# OpenBook_v19.net
KiCad netlist of a schematic drawn in EAGLE
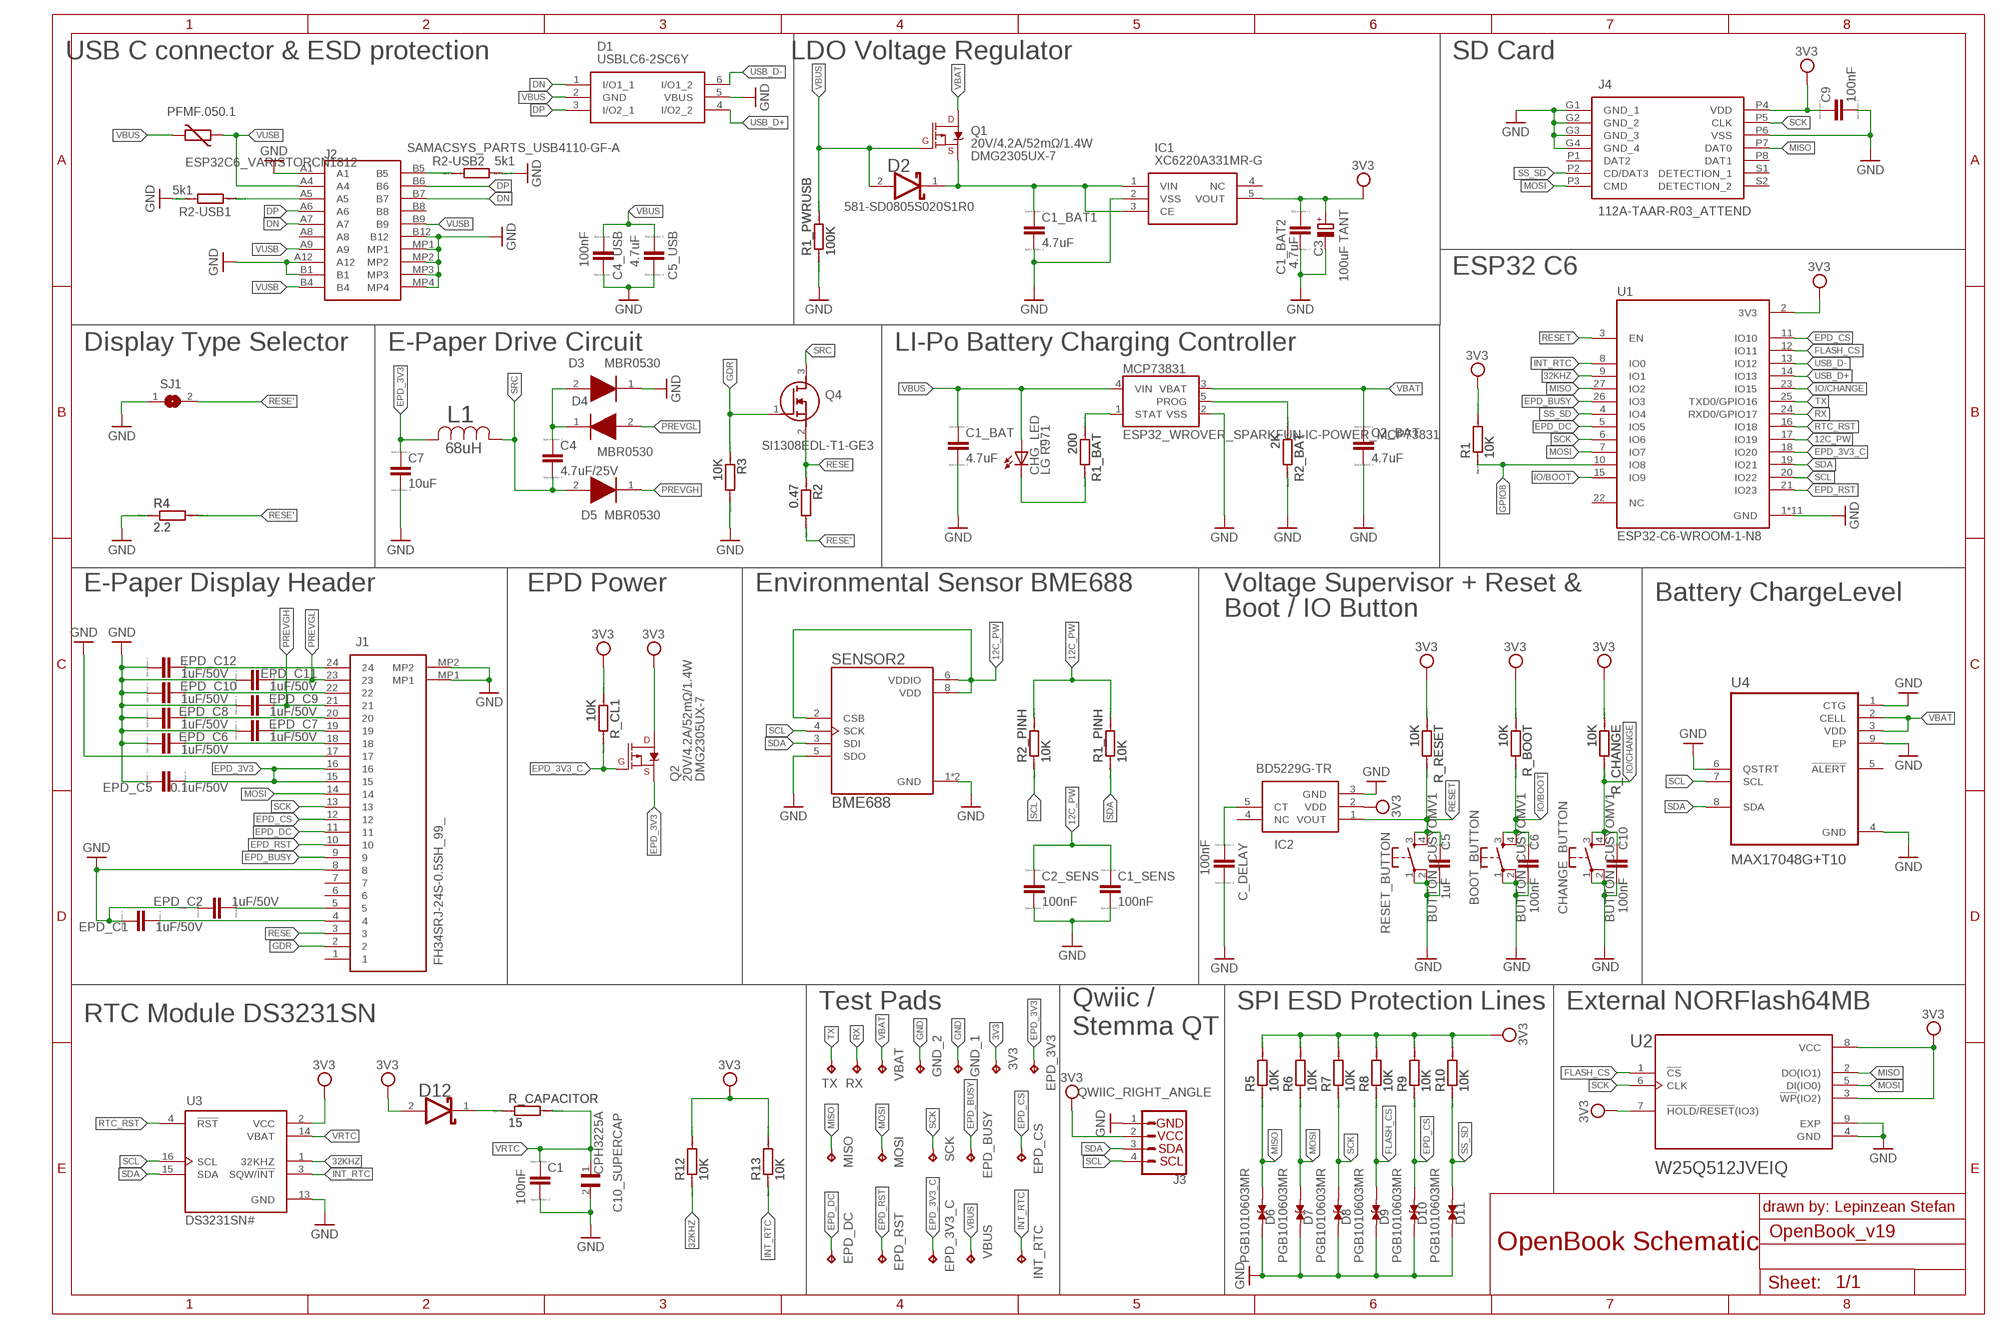
[diagram p0: schematic, sheet 1]

(export (version "E")
  (design (tool "Eeschema 10.0.6"))
  (components
    (comp (ref "3V3")
      (value "TPTP20R")
      (footprint "eagle-import:TP20R")
      (libsource (lib "eagle-import") (part "TPTP20R"))
    )
    (comp (ref "BOOT_BUTTON")
      (value "BUTTON_CUSYOMV1")
      (footprint "eagle-import:MYBUTTON")
      (libsource (lib "eagle-import") (part "BUTTON_CUSYOMV1"))
    )
    (comp (ref "C1")
      (value "100nF")
      (footprint "eagle-import:EAGLE-LTSPICE_C0402")
      (libsource (lib "eagle-import") (part "EAGLE-LTSPICE_CC0402"))
    )
    (comp (ref "C1_BAT")
      (value "4.7uF")
      (footprint "eagle-import:EAGLE-LTSPICE_C0402")
      (libsource (lib "eagle-import") (part "EAGLE-LTSPICE_CC0402"))
    )
    (comp (ref "C1_BAT1")
      (value "4.7uF")
      (footprint "eagle-import:EAGLE-LTSPICE_C0402")
      (libsource (lib "eagle-import") (part "EAGLE-LTSPICE_CC0402"))
    )
    (comp (ref "C1_BAT2")
      (value "4.7uF")
      (footprint "eagle-import:EAGLE-LTSPICE_C0402")
      (libsource (lib "eagle-import") (part "EAGLE-LTSPICE_CC0402"))
    )
    (comp (ref "C1_SENS")
      (value "100nF")
      (footprint "eagle-import:EAGLE-LTSPICE_C0402")
      (libsource (lib "eagle-import") (part "EAGLE-LTSPICE_CC0402"))
    )
    (comp (ref "C2_BAT")
      (value "4.7uF")
      (footprint "eagle-import:EAGLE-LTSPICE_C0402")
      (libsource (lib "eagle-import") (part "EAGLE-LTSPICE_CC0402"))
    )
    (comp (ref "C2_SENS")
      (value "100nF")
      (footprint "eagle-import:EAGLE-LTSPICE_C0402")
      (libsource (lib "eagle-import") (part "EAGLE-LTSPICE_CC0402"))
    )
    (comp (ref "C3")
      (value "100uF TANT")
      (footprint "eagle-import:RCL_CT3528")
      (libsource (lib "eagle-import") (part "RCL_CPOL-EUCT3528"))
    )
    (comp (ref "C4")
      (value "4.7uF/25V")
      (footprint "eagle-import:EAGLE-LTSPICE_C0402")
      (libsource (lib "eagle-import") (part "EAGLE-LTSPICE_CC0402"))
    )
    (comp (ref "C4_USB")
      (value "100nF")
      (footprint "eagle-import:EAGLE-LTSPICE_C0402")
      (libsource (lib "eagle-import") (part "EAGLE-LTSPICE_CC0402"))
    )
    (comp (ref "C5")
      (value "1uF")
      (footprint "eagle-import:EAGLE-LTSPICE_C0402")
      (libsource (lib "eagle-import") (part "EAGLE-LTSPICE_CC0402"))
    )
    (comp (ref "C5_USB")
      (value "4.7uF")
      (footprint "eagle-import:EAGLE-LTSPICE_C0402")
      (libsource (lib "eagle-import") (part "EAGLE-LTSPICE_CC0402"))
    )
    (comp (ref "C6")
      (value "100nF")
      (footprint "eagle-import:EAGLE-LTSPICE_C0402")
      (libsource (lib "eagle-import") (part "EAGLE-LTSPICE_CC0402"))
    )
    (comp (ref "C7")
      (value "10uF")
      (footprint "eagle-import:EAGLE-LTSPICE_C0402")
      (libsource (lib "eagle-import") (part "EAGLE-LTSPICE_CC0402"))
    )
    (comp (ref "C9")
      (value "100nF")
      (footprint "eagle-import:EAGLE-LTSPICE_C0402")
      (libsource (lib "eagle-import") (part "EAGLE-LTSPICE_CC0402"))
    )
    (comp (ref "C10")
      (value "100nF")
      (footprint "eagle-import:EAGLE-LTSPICE_C0402")
      (libsource (lib "eagle-import") (part "EAGLE-LTSPICE_CC0402"))
    )
    (comp (ref "C10_SUPERCAP")
      (value "CPH3225A")
      (footprint "eagle-import:CAPCP3225X100N")
      (fields (field (name "MF") "Seiko Instruments"))
      (libsource (lib "eagle-import") (part "CPH3225A"))
    )
    (comp (ref "CHANGE_BUTTON")
      (value "BUTTON_CUSYOMV1")
      (footprint "eagle-import:MYBUTTON")
      (libsource (lib "eagle-import") (part "BUTTON_CUSYOMV1"))
    )
    (comp (ref "CHG_LED")
      (value "LG R971")
      (footprint "eagle-import:ADAFRUIT_CHIP-LED0603")
      (libsource (lib "eagle-import") (part "ADAFRUIT_LEDCHIP-LED0603"))
    )
    (comp (ref "C_DELAY")
      (value "100nF")
      (footprint "eagle-import:EAGLE-LTSPICE_C0402")
      (libsource (lib "eagle-import") (part "EAGLE-LTSPICE_CC0402"))
    )
    (comp (ref "D1")
      (value "USBLC6-2SC6Y")
      (footprint "eagle-import:SOT95P280X145-6N")
      (fields (field (name "MF") "STMicroelectronics"))
      (libsource (lib "eagle-import") (part "USBLC6-2SC6Y"))
    )
    (comp (ref "D2")
      (value "ESP32_WROVER_AVX---SD0805S020S1R0_AVX_SD0805S020S1R0_0_0AVX_SD0805S020S1R0_0_0")
      (footprint "eagle-import:ESP32_WROVER_AVX---SD0805S020S1R0_AVX_SD0805S020S1R0_0")
      (fields
        (field (name "DIGIKEY_PART_NUMBER") "478-7800-1-ND")
        (field (name "MF") "AVX")
        (field (name "MOUSER_PART_NUMBER") "581-SD0805S020S1R0")
      )
      (libsource (lib "eagle-import") (part "ESP32_WROVER_AVX---SD0805S020S1R0_AVX_SD0805S020S1R0_0_0AVX_SD0805S020S1R0_0_0"))
    )
    (comp (ref "D3")
      (value "MBR0530")
      (footprint "eagle-import:SOD3716X135N")
      (fields (field (name "MF") "ON Semiconductor"))
      (libsource (lib "eagle-import") (part "MBR0530"))
    )
    (comp (ref "D4")
      (value "MBR0530")
      (footprint "eagle-import:SOD3716X135N")
      (fields (field (name "MF") "ON Semiconductor"))
      (libsource (lib "eagle-import") (part "MBR0530"))
    )
    (comp (ref "D5")
      (value "MBR0530")
      (footprint "eagle-import:SOD3716X135N")
      (fields (field (name "MF") "ON Semiconductor"))
      (libsource (lib "eagle-import") (part "MBR0530"))
    )
    (comp (ref "D6")
      (value "PGB1010603MR")
      (footprint "eagle-import:DIOC1608X36N")
      (fields (field (name "MF") "Littelfuse Inc."))
      (libsource (lib "eagle-import") (part "PGB1010603MR"))
    )
    (comp (ref "D7")
      (value "PGB1010603MR")
      (footprint "eagle-import:DIOC1608X36N")
      (fields (field (name "MF") "Littelfuse Inc."))
      (libsource (lib "eagle-import") (part "PGB1010603MR"))
    )
    (comp (ref "D8")
      (value "PGB1010603MR")
      (footprint "eagle-import:DIOC1608X36N")
      (fields (field (name "MF") "Littelfuse Inc."))
      (libsource (lib "eagle-import") (part "PGB1010603MR"))
    )
    (comp (ref "D9")
      (value "PGB1010603MR")
      (footprint "eagle-import:DIOC1608X36N")
      (fields (field (name "MF") "Littelfuse Inc."))
      (libsource (lib "eagle-import") (part "PGB1010603MR"))
    )
    (comp (ref "D10")
      (value "PGB1010603MR")
      (footprint "eagle-import:DIOC1608X36N")
      (fields (field (name "MF") "Littelfuse Inc."))
      (libsource (lib "eagle-import") (part "PGB1010603MR"))
    )
    (comp (ref "D11")
      (value "PGB1010603MR")
      (footprint "eagle-import:DIOC1608X36N")
      (fields (field (name "MF") "Littelfuse Inc."))
      (libsource (lib "eagle-import") (part "PGB1010603MR"))
    )
    (comp (ref "D12")
      (value "ESP32_WROVER_AVX---SD0805S020S1R0_AVX_SD0805S020S1R0_0_0AVX_SD0805S020S1R0_0_0")
      (footprint "eagle-import:ESP32_WROVER_AVX---SD0805S020S1R0_AVX_SD0805S020S1R0_0")
      (fields
        (field (name "DIGIKEY_PART_NUMBER") "478-7800-1-ND")
        (field (name "MF") "AVX")
        (field (name "MOUSER_PART_NUMBER") "581-SD0805S020S1R0")
      )
      (libsource (lib "eagle-import") (part "ESP32_WROVER_AVX---SD0805S020S1R0_AVX_SD0805S020S1R0_0_0AVX_SD0805S020S1R0_0_0"))
    )
    (comp (ref "EPD_3V3")
      (value "TPTP20R")
      (footprint "eagle-import:TP20R")
      (libsource (lib "eagle-import") (part "TPTP20R"))
    )
    (comp (ref "EPD_3V3_C")
      (value "TPTP20R")
      (footprint "eagle-import:TP20R")
      (libsource (lib "eagle-import") (part "TPTP20R"))
    )
    (comp (ref "EPD_BUSY")
      (value "TPTP20R")
      (footprint "eagle-import:TP20R")
      (libsource (lib "eagle-import") (part "TPTP20R"))
    )
    (comp (ref "EPD_C1")
      (value "1uF/50V")
      (footprint "eagle-import:EAGLE-LTSPICE_C0402")
      (libsource (lib "eagle-import") (part "EAGLE-LTSPICE_CC0402"))
    )
    (comp (ref "EPD_C2")
      (value "1uF/50V")
      (footprint "eagle-import:EAGLE-LTSPICE_C0402")
      (libsource (lib "eagle-import") (part "EAGLE-LTSPICE_CC0402"))
    )
    (comp (ref "EPD_C5")
      (value "0.1uF/50V")
      (footprint "eagle-import:EAGLE-LTSPICE_C0402")
      (libsource (lib "eagle-import") (part "EAGLE-LTSPICE_CC0402"))
    )
    (comp (ref "EPD_C6")
      (value "1uF/50V")
      (footprint "eagle-import:EAGLE-LTSPICE_C0402")
      (libsource (lib "eagle-import") (part "EAGLE-LTSPICE_CC0402"))
    )
    (comp (ref "EPD_C7")
      (value "1uF/50V")
      (footprint "eagle-import:EAGLE-LTSPICE_C0402")
      (libsource (lib "eagle-import") (part "EAGLE-LTSPICE_CC0402"))
    )
    (comp (ref "EPD_C8")
      (value "1uF/50V")
      (footprint "eagle-import:EAGLE-LTSPICE_C0402")
      (libsource (lib "eagle-import") (part "EAGLE-LTSPICE_CC0402"))
    )
    (comp (ref "EPD_C9")
      (value "1uF/50V")
      (footprint "eagle-import:EAGLE-LTSPICE_C0402")
      (libsource (lib "eagle-import") (part "EAGLE-LTSPICE_CC0402"))
    )
    (comp (ref "EPD_C10")
      (value "1uF/50V")
      (footprint "eagle-import:EAGLE-LTSPICE_C0402")
      (libsource (lib "eagle-import") (part "EAGLE-LTSPICE_CC0402"))
    )
    (comp (ref "EPD_C11")
      (value "1uF/50V")
      (footprint "eagle-import:EAGLE-LTSPICE_C0402")
      (libsource (lib "eagle-import") (part "EAGLE-LTSPICE_CC0402"))
    )
    (comp (ref "EPD_C12")
      (value "1uF/50V")
      (footprint "eagle-import:EAGLE-LTSPICE_C0402")
      (libsource (lib "eagle-import") (part "EAGLE-LTSPICE_CC0402"))
    )
    (comp (ref "EPD_CS")
      (value "TPTP20R")
      (footprint "eagle-import:TP20R")
      (libsource (lib "eagle-import") (part "TPTP20R"))
    )
    (comp (ref "EPD_DC")
      (value "TPTP20R")
      (footprint "eagle-import:TP20R")
      (libsource (lib "eagle-import") (part "TPTP20R"))
    )
    (comp (ref "EPD_RST")
      (value "TPTP20R")
      (footprint "eagle-import:TP20R")
      (libsource (lib "eagle-import") (part "TPTP20R"))
    )
    (comp (ref "GND_1")
      (value "TPTP20R")
      (footprint "eagle-import:TP20R")
      (libsource (lib "eagle-import") (part "TPTP20R"))
    )
    (comp (ref "GND_2")
      (value "TPTP20R")
      (footprint "eagle-import:TP20R")
      (libsource (lib "eagle-import") (part "TPTP20R"))
    )
    (comp (ref "IC1")
      (value "XC6220A331MR-G")
      (footprint "eagle-import:SOT95P280X125-5N")
      (fields (field (name "MOUSER_PART_NUMBER") "865-XC6220A331MR-G"))
      (libsource (lib "eagle-import") (part "XC6220A331MR-G"))
    )
    (comp (ref "IC2")
      (value "BD5229G-TR")
      (footprint "eagle-import:SOT95P280X120-5N")
      (fields (field (name "MOUSER_PART_NUMBER") "755-BD5229G-TR"))
      (libsource (lib "eagle-import") (part "BD5229G-TR"))
    )
    (comp (ref "INT_RTC")
      (value "TPTP20R")
      (footprint "eagle-import:TP20R")
      (libsource (lib "eagle-import") (part "TPTP20R"))
    )
    (comp (ref "J1")
      (value "FH34SRJ-24S-0.5SH_99_")
      (footprint "eagle-import:FH34SRJ24S05SH99")
      (fields
        (field (name "MANUFACTURER_PART_NUMBER") "FH34SRJ-24S-0.5SH(99)")
        (field (name "MOUSER_PART_NUMBER") "798-FH34SRJ24S05SH99")
      )
      (libsource (lib "eagle-import") (part "FH34SRJ-24S-0.5SH_99_"))
    )
    (comp (ref "J2")
      (value "SAMACSYS_PARTS_USB4110-GF-A")
      (footprint "eagle-import:SAMACSYS_PARTS_USB4110GFA")
      (fields
        (field (name "MANUFACTURER_PART_NUMBER") "USB4110-GF-A")
        (field (name "MOUSER_PART_NUMBER") "640-USB4110-GF-A")
      )
      (libsource (lib "eagle-import") (part "SAMACSYS_PARTS_USB4110-GF-A"))
    )
    (comp (ref "J3")
      (value "QWIIC_RIGHT_ANGLE")
      (footprint "eagle-import:JST04_1MM_RA")
      (libsource (lib "eagle-import") (part "QWIIC_CONNECTORJS-1MM"))
    )
    (comp (ref "J4")
      (value "112A-TAAR-R03_ATTEND")
      (footprint "eagle-import:112ATAARR03ATTEND")
      (fields (field (name "MANUFACTURER_PART_NUMBER") "112A-TAAR-R03 ATTEND"))
      (libsource (lib "eagle-import") (part "112A-TAAR-R03_ATTEND"))
    )
    (comp (ref "L1")
      (value "68uH")
      (footprint "eagle-import:IND_4828-WE-TPC_WRE")
      (fields
        (field (name "MANUFACTURER_PART_NUMBER") "744043680")
        (field (name "COPYRIGHT") "Copyright (C) 2024 Ultra Librarian. All rights reserved.")
      )
      (libsource (lib "eagle-import") (part "744043680IND_4828-WE-TPC_WRE"))
    )
    (comp (ref "MCP73831")
      (value "ESP32_WROVER_SPARKFUN-IC-POWER_MCP73831")
      (footprint "eagle-import:ESP32_WROVER_SPARKFUN-IC-POWER_SOT23-5")
      (libsource (lib "eagle-import") (part "ESP32_WROVER_SPARKFUN-IC-POWER_MCP73831"))
    )
    (comp (ref "MISO")
      (value "TPTP20R")
      (footprint "eagle-import:TP20R")
      (libsource (lib "eagle-import") (part "TPTP20R"))
    )
    (comp (ref "MOSI")
      (value "TPTP20R")
      (footprint "eagle-import:TP20R")
      (libsource (lib "eagle-import") (part "TPTP20R"))
    )
    (comp (ref "PFMF.050.1")
      (value "ESP32C6_VARISTORCN1812")
      (footprint "eagle-import:ESP32C6_VARISTOR_CT_CN1812")
      (libsource (lib "eagle-import") (part "ESP32C6_VARISTORCN1812"))
    )
    (comp (ref "Q1")
      (value "20V/4.2A/52mΩ/1.4W")
      (footprint "eagle-import:ESP32_WROVER_SPARKFUN-DISCRETESEMI_SOT23-3")
      (fields (field (name "PROD_ID") "DMG2305UX-7"))
      (libsource (lib "eagle-import") (part "ESP32_WROVER_SPARKFUN-DISCRETESEMI_MOSFET_PCH-DMG2305UX-7"))
    )
    (comp (ref "Q2")
      (value "20V/4.2A/52mΩ/1.4W")
      (footprint "eagle-import:ESP32_WROVER_SPARKFUN-DISCRETESEMI_SOT23-3")
      (fields (field (name "PROD_ID") "DMG2305UX-7"))
      (libsource (lib "eagle-import") (part "ESP32_WROVER_SPARKFUN-DISCRETESEMI_MOSFET_PCH-DMG2305UX-7"))
    )
    (comp (ref "Q4")
      (value "SI1308EDL-T1-GE3")
      (footprint "eagle-import:SOT65P210X110-3N")
      (fields (field (name "MF") "Vishay Siliconix"))
      (libsource (lib "eagle-import") (part "SI1308EDL-T1-GE3"))
    )
    (comp (ref "R1")
      (value "10K")
      (footprint "eagle-import:R0402")
      (libsource (lib "eagle-import") (part "ESP32_WROVER_EAGLE-LTSPICE_RR0402"))
    )
    (comp (ref "R1_BAT")
      (value "200")
      (footprint "eagle-import:R0402")
      (libsource (lib "eagle-import") (part "ESP32_WROVER_EAGLE-LTSPICE_RR0402"))
    )
    (comp (ref "R1_PINH")
      (value "10K")
      (footprint "eagle-import:R0402")
      (libsource (lib "eagle-import") (part "ESP32_WROVER_EAGLE-LTSPICE_RR0402"))
    )
    (comp (ref "R1_PWRUSB")
      (value "100K")
      (footprint "eagle-import:R0402")
      (libsource (lib "eagle-import") (part "ESP32_WROVER_EAGLE-LTSPICE_RR0402"))
    )
    (comp (ref "R2")
      (value "0.47")
      (footprint "eagle-import:R0402")
      (libsource (lib "eagle-import") (part "ESP32_WROVER_EAGLE-LTSPICE_RR0402"))
    )
    (comp (ref "R2-USB1")
      (value "5k1")
      (footprint "eagle-import:R0402")
      (libsource (lib "eagle-import") (part "ESP32_WROVER_EAGLE-LTSPICE_RR0402"))
    )
    (comp (ref "R2-USB2")
      (value "5k1")
      (footprint "eagle-import:R0402")
      (libsource (lib "eagle-import") (part "ESP32_WROVER_EAGLE-LTSPICE_RR0402"))
    )
    (comp (ref "R2_BAT")
      (value "2K")
      (footprint "eagle-import:R0402")
      (libsource (lib "eagle-import") (part "ESP32_WROVER_EAGLE-LTSPICE_RR0402"))
    )
    (comp (ref "R2_PINH")
      (value "10K")
      (footprint "eagle-import:R0402")
      (libsource (lib "eagle-import") (part "ESP32_WROVER_EAGLE-LTSPICE_RR0402"))
    )
    (comp (ref "R3")
      (value "10K")
      (footprint "eagle-import:R0402")
      (libsource (lib "eagle-import") (part "ESP32_WROVER_EAGLE-LTSPICE_RR0402"))
    )
    (comp (ref "R4")
      (value "2.2")
      (footprint "eagle-import:R0402")
      (libsource (lib "eagle-import") (part "ESP32_WROVER_EAGLE-LTSPICE_RR0402"))
    )
    (comp (ref "R5")
      (value "10K")
      (footprint "eagle-import:R0402")
      (libsource (lib "eagle-import") (part "ESP32_WROVER_EAGLE-LTSPICE_RR0402"))
    )
    (comp (ref "R6")
      (value "10K")
      (footprint "eagle-import:R0402")
      (libsource (lib "eagle-import") (part "ESP32_WROVER_EAGLE-LTSPICE_RR0402"))
    )
    (comp (ref "R7")
      (value "10K")
      (footprint "eagle-import:R0402")
      (libsource (lib "eagle-import") (part "ESP32_WROVER_EAGLE-LTSPICE_RR0402"))
    )
    (comp (ref "R8")
      (value "10K")
      (footprint "eagle-import:R0402")
      (libsource (lib "eagle-import") (part "ESP32_WROVER_EAGLE-LTSPICE_RR0402"))
    )
    (comp (ref "R9")
      (value "10K")
      (footprint "eagle-import:R0402")
      (libsource (lib "eagle-import") (part "ESP32_WROVER_EAGLE-LTSPICE_RR0402"))
    )
    (comp (ref "R10")
      (value "10K")
      (footprint "eagle-import:R0402")
      (libsource (lib "eagle-import") (part "ESP32_WROVER_EAGLE-LTSPICE_RR0402"))
    )
    (comp (ref "R12")
      (value "10K")
      (footprint "eagle-import:R0402")
      (libsource (lib "eagle-import") (part "ESP32_WROVER_EAGLE-LTSPICE_RR0402"))
    )
    (comp (ref "R13")
      (value "10K")
      (footprint "eagle-import:R0402")
      (libsource (lib "eagle-import") (part "ESP32_WROVER_EAGLE-LTSPICE_RR0402"))
    )
    (comp (ref "RESET_BUTTON")
      (value "BUTTON_CUSYOMV1")
      (footprint "eagle-import:MYBUTTON")
      (libsource (lib "eagle-import") (part "BUTTON_CUSYOMV1"))
    )
    (comp (ref "RX")
      (value "TPTP20R")
      (footprint "eagle-import:TP20R")
      (libsource (lib "eagle-import") (part "TPTP20R"))
    )
    (comp (ref "R_BOOT")
      (value "10K")
      (footprint "eagle-import:R0402")
      (libsource (lib "eagle-import") (part "ESP32_WROVER_EAGLE-LTSPICE_RR0402"))
    )
    (comp (ref "R_CAPACITOR")
      (value "15")
      (footprint "eagle-import:R0402")
      (libsource (lib "eagle-import") (part "ESP32_WROVER_EAGLE-LTSPICE_RR0402"))
    )
    (comp (ref "R_CHANGE")
      (value "10K")
      (footprint "eagle-import:R0402")
      (libsource (lib "eagle-import") (part "ESP32_WROVER_EAGLE-LTSPICE_RR0402"))
    )
    (comp (ref "R_CL1")
      (value "10K")
      (footprint "eagle-import:R0402")
      (libsource (lib "eagle-import") (part "ESP32_WROVER_EAGLE-LTSPICE_RR0402"))
    )
    (comp (ref "R_RESET")
      (value "10K")
      (footprint "eagle-import:R0402")
      (libsource (lib "eagle-import") (part "ESP32_WROVER_EAGLE-LTSPICE_RR0402"))
    )
    (comp (ref "SCK")
      (value "TPTP20R")
      (footprint "eagle-import:TP20R")
      (libsource (lib "eagle-import") (part "TPTP20R"))
    )
    (comp (ref "SENSOR2")
      (value "BME688")
      (footprint "eagle-import:ESP32_WROVER_BME680_PSON80P300X300X100-8N")
      (fields (field (name "MF") "Bosch Sensortec") (field (name "MP") "BME680"))
      (libsource (lib "eagle-import") (part "ESP32_WROVER_BME680_BME680"))
    )
    (comp (ref "SJ1") (value "SJ") (footprint "eagle-import:SJ") (libsource (lib "eagle-import") (part "SJ")))
    (comp (ref "TX")
      (value "TPTP20R")
      (footprint "eagle-import:TP20R")
      (libsource (lib "eagle-import") (part "TPTP20R"))
    )
    (comp (ref "U1")
      (value "ESP32-C6-WROOM-1-N8")
      (footprint "eagle-import:XCVR_ESP32-C6-WROOM-1-N8")
      (fields (field (name "MF") "Espressif Systems"))
      (libsource (lib "eagle-import") (part "ESP32-C6-WROOM-1-N8"))
    )
    (comp (ref "U2")
      (value "W25Q512JVEIQ")
      (footprint "eagle-import:SON127P600X800X80-9N")
      (fields (field (name "MF") "Winbond Electronics"))
      (libsource (lib "eagle-import") (part "W25Q512JVEIQ"))
    )
    (comp (ref "U3")
      (value "DS3231SN#")
      (footprint "eagle-import:SOIC127P1032X265-16N")
      (fields (field (name "MF") "Analog Devices"))
      (libsource (lib "eagle-import") (part "DS3231SN#"))
    )
    (comp (ref "U4")
      (value "MAX17048G+T10")
      (footprint "eagle-import:SON50P200X200X80-9N")
      (fields (field (name "MF") "Analog Devices"))
      (libsource (lib "eagle-import") (part "MAX17048G+T10"))
    )
    (comp (ref "VBAT")
      (value "TPTP20R")
      (footprint "eagle-import:TP20R")
      (libsource (lib "eagle-import") (part "TPTP20R"))
    )
    (comp (ref "VBUS")
      (value "TPTP20R")
      (footprint "eagle-import:TP20R")
      (libsource (lib "eagle-import") (part "TPTP20R"))
    )
  )
  (nets
    (net (code "1") (name "3V3") (class "Default")
      (node (ref "3V3") (pin "TP") (pinfunction "TP_TP") (pintype "input"))
      (node (ref "C1_BAT2") (pin "2") (pinfunction "2_2") (pintype "passive"))
      (node (ref "C3") (pin "+") (pinfunction "+_+") (pintype "passive"))
      (node (ref "C9") (pin "1") (pinfunction "1_1") (pintype "passive"))
      (node (ref "D12") (pin "2") (pinfunction "ANODE_2") (pintype "bidirectional"))
      (node (ref "IC1") (pin "5") (pinfunction "VOUT_5") (pintype "bidirectional"))
      (node (ref "IC2") (pin "2") (pinfunction "VDD_2") (pintype "bidirectional"))
      (node (ref "J3") (pin "2") (pinfunction "2_2") (pintype "power_in"))
      (node (ref "J4") (pin "P4") (pinfunction "VDD_P4") (pintype "bidirectional"))
      (node (ref "Q2") (pin "3") (pinfunction "D_3") (pintype "bidirectional"))
      (node (ref "R1") (pin "2") (pinfunction "2_2") (pintype "passive"))
      (node (ref "R10") (pin "2") (pinfunction "2_2") (pintype "passive"))
      (node (ref "R12") (pin "2") (pinfunction "2_2") (pintype "passive"))
      (node (ref "R13") (pin "2") (pinfunction "2_2") (pintype "passive"))
      (node (ref "R5") (pin "2") (pinfunction "2_2") (pintype "passive"))
      (node (ref "R6") (pin "2") (pinfunction "2_2") (pintype "passive"))
      (node (ref "R7") (pin "2") (pinfunction "2_2") (pintype "passive"))
      (node (ref "R8") (pin "2") (pinfunction "2_2") (pintype "passive"))
      (node (ref "R9") (pin "2") (pinfunction "2_2") (pintype "passive"))
      (node (ref "R_BOOT") (pin "1") (pinfunction "1_1") (pintype "passive"))
      (node (ref "R_CHANGE") (pin "1") (pinfunction "1_1") (pintype "passive"))
      (node (ref "R_CL1") (pin "1") (pinfunction "1_1") (pintype "passive"))
      (node (ref "R_RESET") (pin "1") (pinfunction "1_1") (pintype "passive"))
      (node (ref "U1") (pin "2") (pinfunction "3V3_2") (pintype "power_in"))
      (node (ref "U2") (pin "3") (pinfunction "~{WP}(IO2)_3") (pintype "bidirectional"))
      (node (ref "U2") (pin "7") (pinfunction "~{HOLD}/~{RESET}(IO3)_7") (pintype "bidirectional"))
      (node (ref "U2") (pin "8") (pinfunction "VCC_8") (pintype "power_in"))
      (node (ref "U3") (pin "2") (pinfunction "VCC_2") (pintype "power_in"))
    )
    (net (code "2") (name "12C_PW") (class "Default")
      (node (ref "C1_SENS") (pin "1") (pinfunction "1_1") (pintype "passive"))
      (node (ref "C2_SENS") (pin "1") (pinfunction "1_1") (pintype "passive"))
      (node (ref "R1_PINH") (pin "2") (pinfunction "2_2") (pintype "passive"))
      (node (ref "R2_PINH") (pin "2") (pinfunction "2_2") (pintype "passive"))
      (node (ref "SENSOR2") (pin "2") (pinfunction "CSB_2") (pintype "input"))
      (node (ref "SENSOR2") (pin "6") (pinfunction "VDDIO_6") (pintype "power_in"))
      (node (ref "SENSOR2") (pin "8") (pinfunction "VDD_8") (pintype "power_in"))
      (node (ref "U1") (pin "17") (pinfunction "IO19_17") (pintype "bidirectional"))
    )
    (net (code "3") (name "32KHZ") (class "Default")
      (node (ref "R12") (pin "1") (pinfunction "1_1") (pintype "passive"))
      (node (ref "U1") (pin "9") (pinfunction "IO1_9") (pintype "bidirectional"))
      (node (ref "U3") (pin "1") (pinfunction "32KHZ_1") (pintype "output"))
    )
    (net (code "4") (name "DN") (class "Default")
      (node (ref "D1") (pin "1") (pinfunction "I/O1_1_1") (pintype "bidirectional"))
      (node (ref "J2") (pin "A7") (pinfunction "A7_A7") (pintype "bidirectional"))
      (node (ref "J2") (pin "B7") (pinfunction "B7_B7") (pintype "bidirectional"))
    )
    (net (code "5") (name "DP") (class "Default")
      (node (ref "D1") (pin "3") (pinfunction "I/O2_1_3") (pintype "bidirectional"))
      (node (ref "J2") (pin "A6") (pinfunction "A6_A6") (pintype "bidirectional"))
      (node (ref "J2") (pin "B6") (pinfunction "B6_B6") (pintype "bidirectional"))
    )
    (net (code "6") (name "EPD_3V3") (class "Default")
      (node (ref "C7") (pin "1") (pinfunction "1_1") (pintype "passive"))
      (node (ref "EPD_3V3") (pin "TP") (pinfunction "TP_TP") (pintype "input"))
      (node (ref "EPD_C5") (pin "2") (pinfunction "2_2") (pintype "passive"))
      (node (ref "J1") (pin "15") (pinfunction "15_15") (pintype "bidirectional"))
      (node (ref "J1") (pin "16") (pinfunction "16_16") (pintype "bidirectional"))
      (node (ref "L1") (pin "2") (pinfunction "2_2") (pintype "passive"))
      (node (ref "Q2") (pin "2") (pinfunction "S_2") (pintype "bidirectional"))
    )
    (net (code "7") (name "EPD_3V3_C") (class "Default")
      (node (ref "EPD_3V3_C") (pin "TP") (pinfunction "TP_TP") (pintype "input"))
      (node (ref "Q2") (pin "1") (pinfunction "G_1") (pintype "bidirectional"))
      (node (ref "R_CL1") (pin "2") (pinfunction "2_2") (pintype "passive"))
      (node (ref "U1") (pin "18") (pinfunction "IO20_18") (pintype "bidirectional"))
    )
    (net (code "8") (name "EPD_BUSY") (class "Default")
      (node (ref "EPD_BUSY") (pin "TP") (pinfunction "TP_TP") (pintype "input"))
      (node (ref "J1") (pin "9") (pinfunction "9_9") (pintype "bidirectional"))
      (node (ref "U1") (pin "26") (pinfunction "IO3_26") (pintype "bidirectional"))
    )
    (net (code "9") (name "EPD_CS") (class "Default")
      (node (ref "D10") (pin "2") (pinfunction "2_2") (pintype "passive"))
      (node (ref "EPD_CS") (pin "TP") (pinfunction "TP_TP") (pintype "input"))
      (node (ref "J1") (pin "12") (pinfunction "12_12") (pintype "bidirectional"))
      (node (ref "R9") (pin "1") (pinfunction "1_1") (pintype "passive"))
      (node (ref "U1") (pin "11") (pinfunction "IO10_11") (pintype "bidirectional"))
    )
    (net (code "10") (name "EPD_DC") (class "Default")
      (node (ref "EPD_DC") (pin "TP") (pinfunction "TP_TP") (pintype "input"))
      (node (ref "J1") (pin "11") (pinfunction "11_11") (pintype "bidirectional"))
      (node (ref "U1") (pin "5") (pinfunction "IO5_5") (pintype "bidirectional"))
    )
    (net (code "11") (name "EPD_RST") (class "Default")
      (node (ref "EPD_RST") (pin "TP") (pinfunction "TP_TP") (pintype "input"))
      (node (ref "J1") (pin "10") (pinfunction "10_10") (pintype "bidirectional"))
      (node (ref "U1") (pin "21") (pinfunction "IO23_21") (pintype "bidirectional"))
    )
    (net (code "12") (name "FLASH_CS") (class "Default")
      (node (ref "D9") (pin "2") (pinfunction "2_2") (pintype "passive"))
      (node (ref "R8") (pin "1") (pinfunction "1_1") (pintype "passive"))
      (node (ref "U1") (pin "12") (pinfunction "IO11_12") (pintype "bidirectional"))
      (node (ref "U2") (pin "1") (pinfunction "~{CS}_1") (pintype "input"))
    )
    (net (code "13") (name "GDR") (class "Default")
      (node (ref "J1") (pin "2") (pinfunction "2_2") (pintype "bidirectional"))
      (node (ref "Q4") (pin "1") (pinfunction "G_1") (pintype "bidirectional"))
      (node (ref "R3") (pin "1") (pinfunction "1_1") (pintype "passive"))
    )
    (net (code "14") (name "GND") (class "Default")
      (node (ref "BOOT_BUTTON") (pin "1") (pinfunction "1_1") (pintype "passive"))
      (node (ref "BOOT_BUTTON") (pin "2") (pinfunction "2_2") (pintype "passive"))
      (node (ref "C1") (pin "2") (pinfunction "2_2") (pintype "passive"))
      (node (ref "C10") (pin "2") (pinfunction "2_2") (pintype "passive"))
      (node (ref "C10_SUPERCAP") (pin "2") (pinfunction "2_2") (pintype "passive"))
      (node (ref "C1_BAT") (pin "2") (pinfunction "2_2") (pintype "passive"))
      (node (ref "C1_BAT1") (pin "2") (pinfunction "2_2") (pintype "passive"))
      (node (ref "C1_BAT2") (pin "1") (pinfunction "1_1") (pintype "passive"))
      (node (ref "C1_SENS") (pin "2") (pinfunction "2_2") (pintype "passive"))
      (node (ref "C2_BAT") (pin "2") (pinfunction "2_2") (pintype "passive"))
      (node (ref "C2_SENS") (pin "2") (pinfunction "2_2") (pintype "passive"))
      (node (ref "C3") (pin "-") (pinfunction "-_-") (pintype "passive"))
      (node (ref "C4_USB") (pin "2") (pinfunction "2_2") (pintype "passive"))
      (node (ref "C5") (pin "2") (pinfunction "2_2") (pintype "passive"))
      (node (ref "C5_USB") (pin "2") (pinfunction "2_2") (pintype "passive"))
      (node (ref "C6") (pin "2") (pinfunction "2_2") (pintype "passive"))
      (node (ref "C7") (pin "2") (pinfunction "2_2") (pintype "passive"))
      (node (ref "C9") (pin "2") (pinfunction "2_2") (pintype "passive"))
      (node (ref "CHANGE_BUTTON") (pin "1") (pinfunction "1_1") (pintype "passive"))
      (node (ref "CHANGE_BUTTON") (pin "2") (pinfunction "2_2") (pintype "passive"))
      (node (ref "C_DELAY") (pin "2") (pinfunction "2_2") (pintype "passive"))
      (node (ref "D1") (pin "5") (pinfunction "VBUS_5") (pintype "bidirectional"))
      (node (ref "D10") (pin "1") (pinfunction "1_1") (pintype "passive"))
      (node (ref "D11") (pin "1") (pinfunction "1_1") (pintype "passive"))
      (node (ref "D3") (pin "1") (pinfunction "K_1") (pintype "bidirectional"))
      (node (ref "D6") (pin "1") (pinfunction "1_1") (pintype "passive"))
      (node (ref "D7") (pin "1") (pinfunction "1_1") (pintype "passive"))
      (node (ref "D8") (pin "1") (pinfunction "1_1") (pintype "passive"))
      (node (ref "D9") (pin "1") (pinfunction "1_1") (pintype "passive"))
      (node (ref "EPD_C1") (pin "1") (pinfunction "1_1") (pintype "passive"))
      (node (ref "EPD_C10") (pin "1") (pinfunction "1_1") (pintype "passive"))
      (node (ref "EPD_C11") (pin "1") (pinfunction "1_1") (pintype "passive"))
      (node (ref "EPD_C12") (pin "1") (pinfunction "1_1") (pintype "passive"))
      (node (ref "EPD_C2") (pin "1") (pinfunction "1_1") (pintype "passive"))
      (node (ref "EPD_C5") (pin "1") (pinfunction "1_1") (pintype "passive"))
      (node (ref "EPD_C6") (pin "1") (pinfunction "1_1") (pintype "passive"))
      (node (ref "EPD_C7") (pin "1") (pinfunction "1_1") (pintype "passive"))
      (node (ref "EPD_C8") (pin "1") (pinfunction "1_1") (pintype "passive"))
      (node (ref "EPD_C9") (pin "1") (pinfunction "1_1") (pintype "passive"))
      (node (ref "GND_1") (pin "TP") (pinfunction "TP_TP") (pintype "input"))
      (node (ref "GND_2") (pin "TP") (pinfunction "TP_TP") (pintype "input"))
      (node (ref "IC1") (pin "2") (pinfunction "VSS_2") (pintype "bidirectional"))
      (node (ref "IC2") (pin "3") (pinfunction "GND_3") (pintype "bidirectional"))
      (node (ref "J1") (pin "17") (pinfunction "17_17") (pintype "bidirectional"))
      (node (ref "J1") (pin "8") (pinfunction "8_8") (pintype "bidirectional"))
      (node (ref "J1") (pin "MP1") (pinfunction "MP1_MP1") (pintype "bidirectional"))
      (node (ref "J1") (pin "MP2") (pinfunction "MP2_MP2") (pintype "bidirectional"))
      (node (ref "J2") (pin "A1") (pinfunction "A1_A1") (pintype "bidirectional"))
      (node (ref "J2") (pin "A12") (pinfunction "A12_A12") (pintype "bidirectional"))
      (node (ref "J2") (pin "B1") (pinfunction "B1_B1") (pintype "bidirectional"))
      (node (ref "J2") (pin "B12") (pinfunction "B12_B12") (pintype "bidirectional"))
      (node (ref "J2") (pin "MP1") (pinfunction "MP1_MP1") (pintype "bidirectional"))
      (node (ref "J2") (pin "MP2") (pinfunction "MP2_MP2") (pintype "bidirectional"))
      (node (ref "J2") (pin "MP3") (pinfunction "MP3_MP3") (pintype "bidirectional"))
      (node (ref "J2") (pin "MP4") (pinfunction "MP4_MP4") (pintype "bidirectional"))
      (node (ref "J3") (pin "1") (pinfunction "1_1") (pintype "power_in"))
      (node (ref "J4") (pin "G1") (pinfunction "GND_1_G1") (pintype "bidirectional"))
      (node (ref "J4") (pin "G2") (pinfunction "GND_2_G2") (pintype "bidirectional"))
      (node (ref "J4") (pin "G3") (pinfunction "GND_3_G3") (pintype "bidirectional"))
      (node (ref "J4") (pin "G4") (pinfunction "GND_4_G4") (pintype "bidirectional"))
      (node (ref "J4") (pin "P6") (pinfunction "VSS_P6") (pintype "bidirectional"))
      (node (ref "MCP73831") (pin "2") (pinfunction "VSS_2") (pintype "power_in"))
      (node (ref "R1_PWRUSB") (pin "1") (pinfunction "1_1") (pintype "passive"))
      (node (ref "R2-USB1") (pin "1") (pinfunction "1_1") (pintype "passive"))
      (node (ref "R2-USB2") (pin "2") (pinfunction "2_2") (pintype "passive"))
      (node (ref "R2_BAT") (pin "2") (pinfunction "2_2") (pintype "passive"))
      (node (ref "R3") (pin "2") (pinfunction "2_2") (pintype "passive"))
      (node (ref "R4") (pin "1") (pinfunction "1_1") (pintype "passive"))
      (node (ref "RESET_BUTTON") (pin "1") (pinfunction "1_1") (pintype "passive"))
      (node (ref "RESET_BUTTON") (pin "2") (pinfunction "2_2") (pintype "passive"))
      (node (ref "SENSOR2") (pin "1") (pinfunction "GND_1") (pintype "power_in"))
      (node (ref "SENSOR2") (pin "5") (pinfunction "SDO_5") (pintype "bidirectional"))
      (node (ref "SENSOR2") (pin "7") (pinfunction "GND_7") (pintype "power_in"))
      (node (ref "SJ1") (pin "1") (pinfunction "1_1") (pintype "passive"))
      (node (ref "U1") (pin "1") (pinfunction "GND_1") (pintype "power_in"))
      (node (ref "U1") (pin "28") (pinfunction "GND_28") (pintype "power_in"))
      (node (ref "U1") (pin "29_1") (pinfunction "GND_29_1") (pintype "power_in"))
      (node (ref "U1") (pin "29_2") (pinfunction "GND_29_2") (pintype "power_in"))
      (node (ref "U1") (pin "29_3") (pinfunction "GND_29_3") (pintype "power_in"))
      (node (ref "U1") (pin "29_4") (pinfunction "GND_29_4") (pintype "power_in"))
      (node (ref "U1") (pin "29_5") (pinfunction "GND_29_5") (pintype "power_in"))
      (node (ref "U1") (pin "29_6") (pinfunction "GND_29_6") (pintype "power_in"))
      (node (ref "U1") (pin "29_7") (pinfunction "GND_29_7") (pintype "power_in"))
      (node (ref "U1") (pin "29_8") (pinfunction "GND_29_8") (pintype "power_in"))
      (node (ref "U1") (pin "29_9") (pinfunction "GND_29_9") (pintype "power_in"))
      (node (ref "U2") (pin "4") (pinfunction "GND_4") (pintype "power_in"))
      (node (ref "U2") (pin "9") (pinfunction "EXP_9") (pintype "passive"))
      (node (ref "U3") (pin "13") (pinfunction "GND_13") (pintype "power_in"))
      (node (ref "U4") (pin "1") (pinfunction "CTG_1") (pintype "power_in"))
      (node (ref "U4") (pin "4") (pinfunction "GND_4") (pintype "power_in"))
      (node (ref "U4") (pin "6") (pinfunction "QSTRT_6") (pintype "input"))
      (node (ref "U4") (pin "9") (pinfunction "EP_9") (pintype "power_in"))
    )
    (net (code "15") (name "GPIO8") (class "Default")
      (node (ref "R1") (pin "1") (pinfunction "1_1") (pintype "passive"))
      (node (ref "U1") (pin "10") (pinfunction "IO8_10") (pintype "bidirectional"))
    )
    (net (code "16") (name "INT_RTC") (class "Default")
      (node (ref "INT_RTC") (pin "TP") (pinfunction "TP_TP") (pintype "input"))
      (node (ref "R13") (pin "1") (pinfunction "1_1") (pintype "passive"))
      (node (ref "U1") (pin "8") (pinfunction "IO0_8") (pintype "bidirectional"))
      (node (ref "U3") (pin "3") (pinfunction "SQW/~{INT}_3") (pintype "output"))
    )
    (net (code "17") (name "IO{slash}BOOT") (class "Default")
      (node (ref "BOOT_BUTTON") (pin "3") (pinfunction "3_3") (pintype "passive"))
      (node (ref "BOOT_BUTTON") (pin "4") (pinfunction "4_4") (pintype "passive"))
      (node (ref "C6") (pin "1") (pinfunction "1_1") (pintype "passive"))
      (node (ref "R_BOOT") (pin "2") (pinfunction "2_2") (pintype "passive"))
      (node (ref "U1") (pin "15") (pinfunction "IO9_15") (pintype "bidirectional"))
    )
    (net (code "18") (name "IO{slash}CHANGE") (class "Default")
      (node (ref "C10") (pin "1") (pinfunction "1_1") (pintype "passive"))
      (node (ref "CHANGE_BUTTON") (pin "3") (pinfunction "3_3") (pintype "passive"))
      (node (ref "CHANGE_BUTTON") (pin "4") (pinfunction "4_4") (pintype "passive"))
      (node (ref "R_CHANGE") (pin "2") (pinfunction "2_2") (pintype "passive"))
      (node (ref "U1") (pin "23") (pinfunction "IO15_23") (pintype "bidirectional"))
    )
    (net (code "19") (name "MISO") (class "Default")
      (node (ref "D6") (pin "2") (pinfunction "2_2") (pintype "passive"))
      (node (ref "J4") (pin "P7") (pinfunction "DAT0_P7") (pintype "bidirectional"))
      (node (ref "MISO") (pin "TP") (pinfunction "TP_TP") (pintype "input"))
      (node (ref "R5") (pin "1") (pinfunction "1_1") (pintype "passive"))
      (node (ref "U1") (pin "27") (pinfunction "IO2_27") (pintype "bidirectional"))
      (node (ref "U2") (pin "2") (pinfunction "DO(IO1)_2") (pintype "bidirectional"))
    )
    (net (code "20") (name "MOSI") (class "Default")
      (node (ref "D7") (pin "2") (pinfunction "2_2") (pintype "passive"))
      (node (ref "J1") (pin "14") (pinfunction "14_14") (pintype "bidirectional"))
      (node (ref "J4") (pin "P3") (pinfunction "CMD_P3") (pintype "bidirectional"))
      (node (ref "MOSI") (pin "TP") (pinfunction "TP_TP") (pintype "input"))
      (node (ref "R6") (pin "1") (pinfunction "1_1") (pintype "passive"))
      (node (ref "U1") (pin "7") (pinfunction "IO7_7") (pintype "bidirectional"))
      (node (ref "U2") (pin "5") (pinfunction "DI(IO0)_5") (pintype "bidirectional"))
    )
    (net (code "21") (name "Net-(CHG_LED-PadC)") (class "Default")
      (node (ref "CHG_LED") (pin "C") (pinfunction "C_C") (pintype "passive"))
      (node (ref "R1_BAT") (pin "2") (pinfunction "2_2") (pintype "passive"))
    )
    (net (code "22") (name "Net-(D2-CATHODE)") (class "Default")
      (node (ref "C1_BAT1") (pin "1") (pinfunction "1_1") (pintype "passive"))
      (node (ref "D2") (pin "1") (pinfunction "CATHODE_1") (pintype "bidirectional"))
      (node (ref "IC1") (pin "1") (pinfunction "VIN_1") (pintype "bidirectional"))
      (node (ref "IC1") (pin "3") (pinfunction "CE_3") (pintype "bidirectional"))
      (node (ref "Q1") (pin "2") (pinfunction "S_2") (pintype "bidirectional"))
    )
    (net (code "23") (name "Net-(D3-A)") (class "Default")
      (node (ref "C4") (pin "1") (pinfunction "1_1") (pintype "passive"))
      (node (ref "D3") (pin "2") (pinfunction "A_2") (pintype "bidirectional"))
      (node (ref "D4") (pin "1") (pinfunction "K_1") (pintype "bidirectional"))
    )
    (net (code "24") (name "Net-(D12-CATHODE)") (class "Default")
      (node (ref "D12") (pin "1") (pinfunction "CATHODE_1") (pintype "bidirectional"))
      (node (ref "R_CAPACITOR") (pin "1") (pinfunction "1_1") (pintype "passive"))
    )
    (net (code "25") (name "Net-(EPD_C1-Pad2)") (class "Default")
      (node (ref "EPD_C1") (pin "2") (pinfunction "2_2") (pintype "passive"))
      (node (ref "J1") (pin "4") (pinfunction "4_4") (pintype "bidirectional"))
    )
    (net (code "26") (name "Net-(EPD_C2-Pad2)") (class "Default")
      (node (ref "EPD_C2") (pin "2") (pinfunction "2_2") (pintype "passive"))
      (node (ref "J1") (pin "5") (pinfunction "5_5") (pintype "bidirectional"))
    )
    (net (code "27") (name "Net-(EPD_C6-Pad2)") (class "Default")
      (node (ref "EPD_C6") (pin "2") (pinfunction "2_2") (pintype "passive"))
      (node (ref "J1") (pin "18") (pinfunction "18_18") (pintype "bidirectional"))
    )
    (net (code "28") (name "Net-(EPD_C7-Pad2)") (class "Default")
      (node (ref "EPD_C7") (pin "2") (pinfunction "2_2") (pintype "passive"))
      (node (ref "J1") (pin "19") (pinfunction "19_19") (pintype "bidirectional"))
    )
    (net (code "29") (name "Net-(EPD_C8-Pad2)") (class "Default")
      (node (ref "EPD_C8") (pin "2") (pinfunction "2_2") (pintype "passive"))
      (node (ref "J1") (pin "20") (pinfunction "20_20") (pintype "bidirectional"))
    )
    (net (code "30") (name "Net-(EPD_C10-Pad2)") (class "Default")
      (node (ref "EPD_C10") (pin "2") (pinfunction "2_2") (pintype "passive"))
      (node (ref "J1") (pin "22") (pinfunction "22_22") (pintype "bidirectional"))
    )
    (net (code "31") (name "Net-(EPD_C12-Pad2)") (class "Default")
      (node (ref "EPD_C12") (pin "2") (pinfunction "2_2") (pintype "passive"))
      (node (ref "J1") (pin "24") (pinfunction "24_24") (pintype "bidirectional"))
    )
    (net (code "32") (name "Net-(IC2-CT)") (class "Default")
      (node (ref "C_DELAY") (pin "1") (pinfunction "1_1") (pintype "passive"))
      (node (ref "IC2") (pin "5") (pinfunction "CT_5") (pintype "bidirectional"))
    )
    (net (code "33") (name "Net-(J2-PadA5)") (class "Default")
      (node (ref "J2") (pin "A5") (pinfunction "A5_A5") (pintype "bidirectional"))
      (node (ref "R2-USB1") (pin "2") (pinfunction "2_2") (pintype "passive"))
    )
    (net (code "34") (name "Net-(J2-PadB5)") (class "Default")
      (node (ref "J2") (pin "B5") (pinfunction "B5_B5") (pintype "bidirectional"))
      (node (ref "R2-USB2") (pin "1") (pinfunction "1_1") (pintype "passive"))
    )
    (net (code "35") (name "Net-(MCP73831-PROG)") (class "Default")
      (node (ref "MCP73831") (pin "5") (pinfunction "PROG_5") (pintype "input"))
      (node (ref "R2_BAT") (pin "1") (pinfunction "1_1") (pintype "passive"))
    )
    (net (code "36") (name "Net-(MCP73831-STAT)") (class "Default")
      (node (ref "MCP73831") (pin "1") (pinfunction "STAT_1") (pintype "output"))
      (node (ref "R1_BAT") (pin "1") (pinfunction "1_1") (pintype "passive"))
    )
    (net (code "37") (name "PREVGH") (class "Default")
      (node (ref "D5") (pin "1") (pinfunction "K_1") (pintype "bidirectional"))
      (node (ref "EPD_C9") (pin "2") (pinfunction "2_2") (pintype "passive"))
      (node (ref "J1") (pin "21") (pinfunction "21_21") (pintype "bidirectional"))
    )
    (net (code "38") (name "PREVGL") (class "Default")
      (node (ref "D4") (pin "2") (pinfunction "A_2") (pintype "bidirectional"))
      (node (ref "EPD_C11") (pin "2") (pinfunction "2_2") (pintype "passive"))
      (node (ref "J1") (pin "23") (pinfunction "23_23") (pintype "bidirectional"))
    )
    (net (code "39") (name "RESE") (class "Default")
      (node (ref "J1") (pin "3") (pinfunction "3_3") (pintype "bidirectional"))
      (node (ref "Q4") (pin "2") (pinfunction "S_2") (pintype "bidirectional"))
      (node (ref "R2") (pin "1") (pinfunction "1_1") (pintype "passive"))
    )
    (net (code "40") (name "RESE'") (class "Default")
      (node (ref "R2") (pin "2") (pinfunction "2_2") (pintype "passive"))
      (node (ref "R4") (pin "2") (pinfunction "2_2") (pintype "passive"))
      (node (ref "SJ1") (pin "2") (pinfunction "2_2") (pintype "passive"))
    )
    (net (code "41") (name "RESET") (class "Default")
      (node (ref "C5") (pin "1") (pinfunction "1_1") (pintype "passive"))
      (node (ref "IC2") (pin "1") (pinfunction "VOUT_1") (pintype "bidirectional"))
      (node (ref "RESET_BUTTON") (pin "3") (pinfunction "3_3") (pintype "passive"))
      (node (ref "RESET_BUTTON") (pin "4") (pinfunction "4_4") (pintype "passive"))
      (node (ref "R_RESET") (pin "2") (pinfunction "2_2") (pintype "passive"))
      (node (ref "U1") (pin "3") (pinfunction "EN_3") (pintype "input"))
    )
    (net (code "42") (name "RTC_RST") (class "Default")
      (node (ref "U1") (pin "16") (pinfunction "IO18_16") (pintype "bidirectional"))
      (node (ref "U3") (pin "4") (pinfunction "~{RST}_4") (pintype "input"))
    )
    (net (code "43") (name "RX") (class "Default")
      (node (ref "RX") (pin "TP") (pinfunction "TP_TP") (pintype "input"))
      (node (ref "U1") (pin "24") (pinfunction "RXD0/GPIO17_24") (pintype "bidirectional"))
    )
    (net (code "44") (name "SCK") (class "Default")
      (node (ref "D8") (pin "2") (pinfunction "2_2") (pintype "passive"))
      (node (ref "J1") (pin "13") (pinfunction "13_13") (pintype "bidirectional"))
      (node (ref "J4") (pin "P5") (pinfunction "CLK_P5") (pintype "bidirectional"))
      (node (ref "R7") (pin "1") (pinfunction "1_1") (pintype "passive"))
      (node (ref "SCK") (pin "TP") (pinfunction "TP_TP") (pintype "input"))
      (node (ref "U1") (pin "6") (pinfunction "IO6_6") (pintype "bidirectional"))
      (node (ref "U2") (pin "6") (pinfunction "CLK_6") (pintype "input"))
    )
    (net (code "45") (name "SCL") (class "Default")
      (node (ref "J3") (pin "4") (pinfunction "4_4") (pintype "passive"))
      (node (ref "R2_PINH") (pin "1") (pinfunction "1_1") (pintype "passive"))
      (node (ref "SENSOR2") (pin "4") (pinfunction "SCK_4") (pintype "input"))
      (node (ref "U1") (pin "20") (pinfunction "IO22_20") (pintype "bidirectional"))
      (node (ref "U3") (pin "16") (pinfunction "SCL_16") (pintype "input"))
      (node (ref "U4") (pin "7") (pinfunction "SCL_7") (pintype "input"))
    )
    (net (code "46") (name "SDA") (class "Default")
      (node (ref "J3") (pin "3") (pinfunction "3_3") (pintype "passive"))
      (node (ref "R1_PINH") (pin "1") (pinfunction "1_1") (pintype "passive"))
      (node (ref "SENSOR2") (pin "3") (pinfunction "SDI_3") (pintype "bidirectional"))
      (node (ref "U1") (pin "19") (pinfunction "IO21_19") (pintype "bidirectional"))
      (node (ref "U3") (pin "15") (pinfunction "SDA_15") (pintype "bidirectional"))
      (node (ref "U4") (pin "8") (pinfunction "SDA_8") (pintype "bidirectional"))
    )
    (net (code "47") (name "SRC") (class "Default")
      (node (ref "C4") (pin "2") (pinfunction "2_2") (pintype "passive"))
      (node (ref "D5") (pin "2") (pinfunction "A_2") (pintype "bidirectional"))
      (node (ref "L1") (pin "1") (pinfunction "1_1") (pintype "passive"))
      (node (ref "Q4") (pin "3") (pinfunction "D_3") (pintype "bidirectional"))
    )
    (net (code "48") (name "SS_SD") (class "Default")
      (node (ref "D11") (pin "2") (pinfunction "2_2") (pintype "passive"))
      (node (ref "J4") (pin "P2") (pinfunction "CD/DAT3_P2") (pintype "bidirectional"))
      (node (ref "R10") (pin "1") (pinfunction "1_1") (pintype "passive"))
      (node (ref "U1") (pin "4") (pinfunction "IO4_4") (pintype "bidirectional"))
    )
    (net (code "49") (name "TX") (class "Default")
      (node (ref "TX") (pin "TP") (pinfunction "TP_TP") (pintype "input"))
      (node (ref "U1") (pin "25") (pinfunction "TXD0/GPIO16_25") (pintype "bidirectional"))
    )
    (net (code "50") (name "USB_D+") (class "Default")
      (node (ref "D1") (pin "4") (pinfunction "I/O2_2_4") (pintype "bidirectional"))
      (node (ref "U1") (pin "14") (pinfunction "IO13_14") (pintype "bidirectional"))
    )
    (net (code "51") (name "USB_D-") (class "Default")
      (node (ref "D1") (pin "6") (pinfunction "I/O1_2_6") (pintype "bidirectional"))
      (node (ref "U1") (pin "13") (pinfunction "IO12_13") (pintype "bidirectional"))
    )
    (net (code "52") (name "VBAT") (class "Default")
      (node (ref "C2_BAT") (pin "1") (pinfunction "1_1") (pintype "passive"))
      (node (ref "MCP73831") (pin "3") (pinfunction "VBAT_3") (pintype "power_in"))
      (node (ref "Q1") (pin "3") (pinfunction "D_3") (pintype "bidirectional"))
      (node (ref "U4") (pin "2") (pinfunction "CELL_2") (pintype "power_in"))
      (node (ref "U4") (pin "3") (pinfunction "VDD_3") (pintype "power_in"))
      (node (ref "VBAT") (pin "TP") (pinfunction "TP_TP") (pintype "input"))
    )
    (net (code "53") (name "VBUS") (class "Default")
      (node (ref "C1_BAT") (pin "1") (pinfunction "1_1") (pintype "passive"))
      (node (ref "C4_USB") (pin "1") (pinfunction "1_1") (pintype "passive"))
      (node (ref "C5_USB") (pin "1") (pinfunction "1_1") (pintype "passive"))
      (node (ref "CHG_LED") (pin "A") (pinfunction "A_A") (pintype "passive"))
      (node (ref "D1") (pin "2") (pinfunction "GND_2") (pintype "bidirectional"))
      (node (ref "D2") (pin "2") (pinfunction "ANODE_2") (pintype "bidirectional"))
      (node (ref "MCP73831") (pin "4") (pinfunction "VIN_4") (pintype "power_in"))
      (node (ref "PFMF.050.1") (pin "2") (pinfunction "2_2") (pintype "passive"))
      (node (ref "Q1") (pin "1") (pinfunction "G_1") (pintype "bidirectional"))
      (node (ref "R1_PWRUSB") (pin "2") (pinfunction "2_2") (pintype "passive"))
      (node (ref "VBUS") (pin "TP") (pinfunction "TP_TP") (pintype "input"))
    )
    (net (code "54") (name "VRTC") (class "Default")
      (node (ref "C1") (pin "1") (pinfunction "1_1") (pintype "passive"))
      (node (ref "C10_SUPERCAP") (pin "1") (pinfunction "1_1") (pintype "passive"))
      (node (ref "R_CAPACITOR") (pin "2") (pinfunction "2_2") (pintype "passive"))
      (node (ref "U3") (pin "14") (pinfunction "VBAT_14") (pintype "power_in"))
    )
    (net (code "55") (name "VUSB") (class "Default")
      (node (ref "J2") (pin "A4") (pinfunction "A4_A4") (pintype "bidirectional"))
      (node (ref "J2") (pin "A9") (pinfunction "A9_A9") (pintype "bidirectional"))
      (node (ref "J2") (pin "B4") (pinfunction "B4_B4") (pintype "bidirectional"))
      (node (ref "J2") (pin "B9") (pinfunction "B9_B9") (pintype "bidirectional"))
      (node (ref "PFMF.050.1") (pin "1") (pinfunction "1_1") (pintype "passive"))
    )
    (net (code "56") (name "unconnected-(IC1-NC-Pad4)") (class "Default")
      (node (ref "IC1") (pin "4") (pinfunction "NC_4") (pintype "no_connect"))
    )
    (net (code "57") (name "unconnected-(IC2-NC-Pad4)") (class "Default")
      (node (ref "IC2") (pin "4") (pinfunction "NC_4") (pintype "no_connect"))
    )
    (net (code "58") (name "unconnected-(J1-Pad1)") (class "Default")
      (node (ref "J1") (pin "1") (pinfunction "1_1") (pintype "bidirectional"))
    )
    (net (code "59") (name "unconnected-(J1-Pad6)") (class "Default")
      (node (ref "J1") (pin "6") (pinfunction "6_6") (pintype "bidirectional"))
    )
    (net (code "60") (name "unconnected-(J1-Pad7)") (class "Default")
      (node (ref "J1") (pin "7") (pinfunction "7_7") (pintype "bidirectional"))
    )
    (net (code "61") (name "unconnected-(J2-PadA8)") (class "Default")
      (node (ref "J2") (pin "A8") (pinfunction "A8_A8") (pintype "bidirectional"))
    )
    (net (code "62") (name "unconnected-(J2-PadB8)") (class "Default")
      (node (ref "J2") (pin "B8") (pinfunction "B8_B8") (pintype "bidirectional"))
    )
    (net (code "63") (name "unconnected-(J4-DAT1-PadP8)") (class "Default")
      (node (ref "J4") (pin "P8") (pinfunction "DAT1_P8") (pintype "bidirectional"))
    )
    (net (code "64") (name "unconnected-(J4-DAT2-PadP1)") (class "Default")
      (node (ref "J4") (pin "P1") (pinfunction "DAT2_P1") (pintype "bidirectional"))
    )
    (net (code "65") (name "unconnected-(J4-DETECTION_1-PadS1)") (class "Default")
      (node (ref "J4") (pin "S1") (pinfunction "DETECTION_1_S1") (pintype "bidirectional"))
    )
    (net (code "66") (name "unconnected-(J4-DETECTION_2-PadS2)") (class "Default")
      (node (ref "J4") (pin "S2") (pinfunction "DETECTION_2_S2") (pintype "bidirectional"))
    )
    (net (code "67") (name "unconnected-(U1-NC-Pad22)") (class "Default")
      (node (ref "U1") (pin "22") (pinfunction "NC_22") (pintype "no_connect"))
    )
    (net (code "68") (name "unconnected-(U4-~{ALERT}-Pad5)") (class "Default")
      (node (ref "U4") (pin "5") (pinfunction "~{ALERT}_5") (pintype "output"))
    )
  )
)
